# ESP32S3.net
KiCad netlist of a schematic drawn in Altium Designer
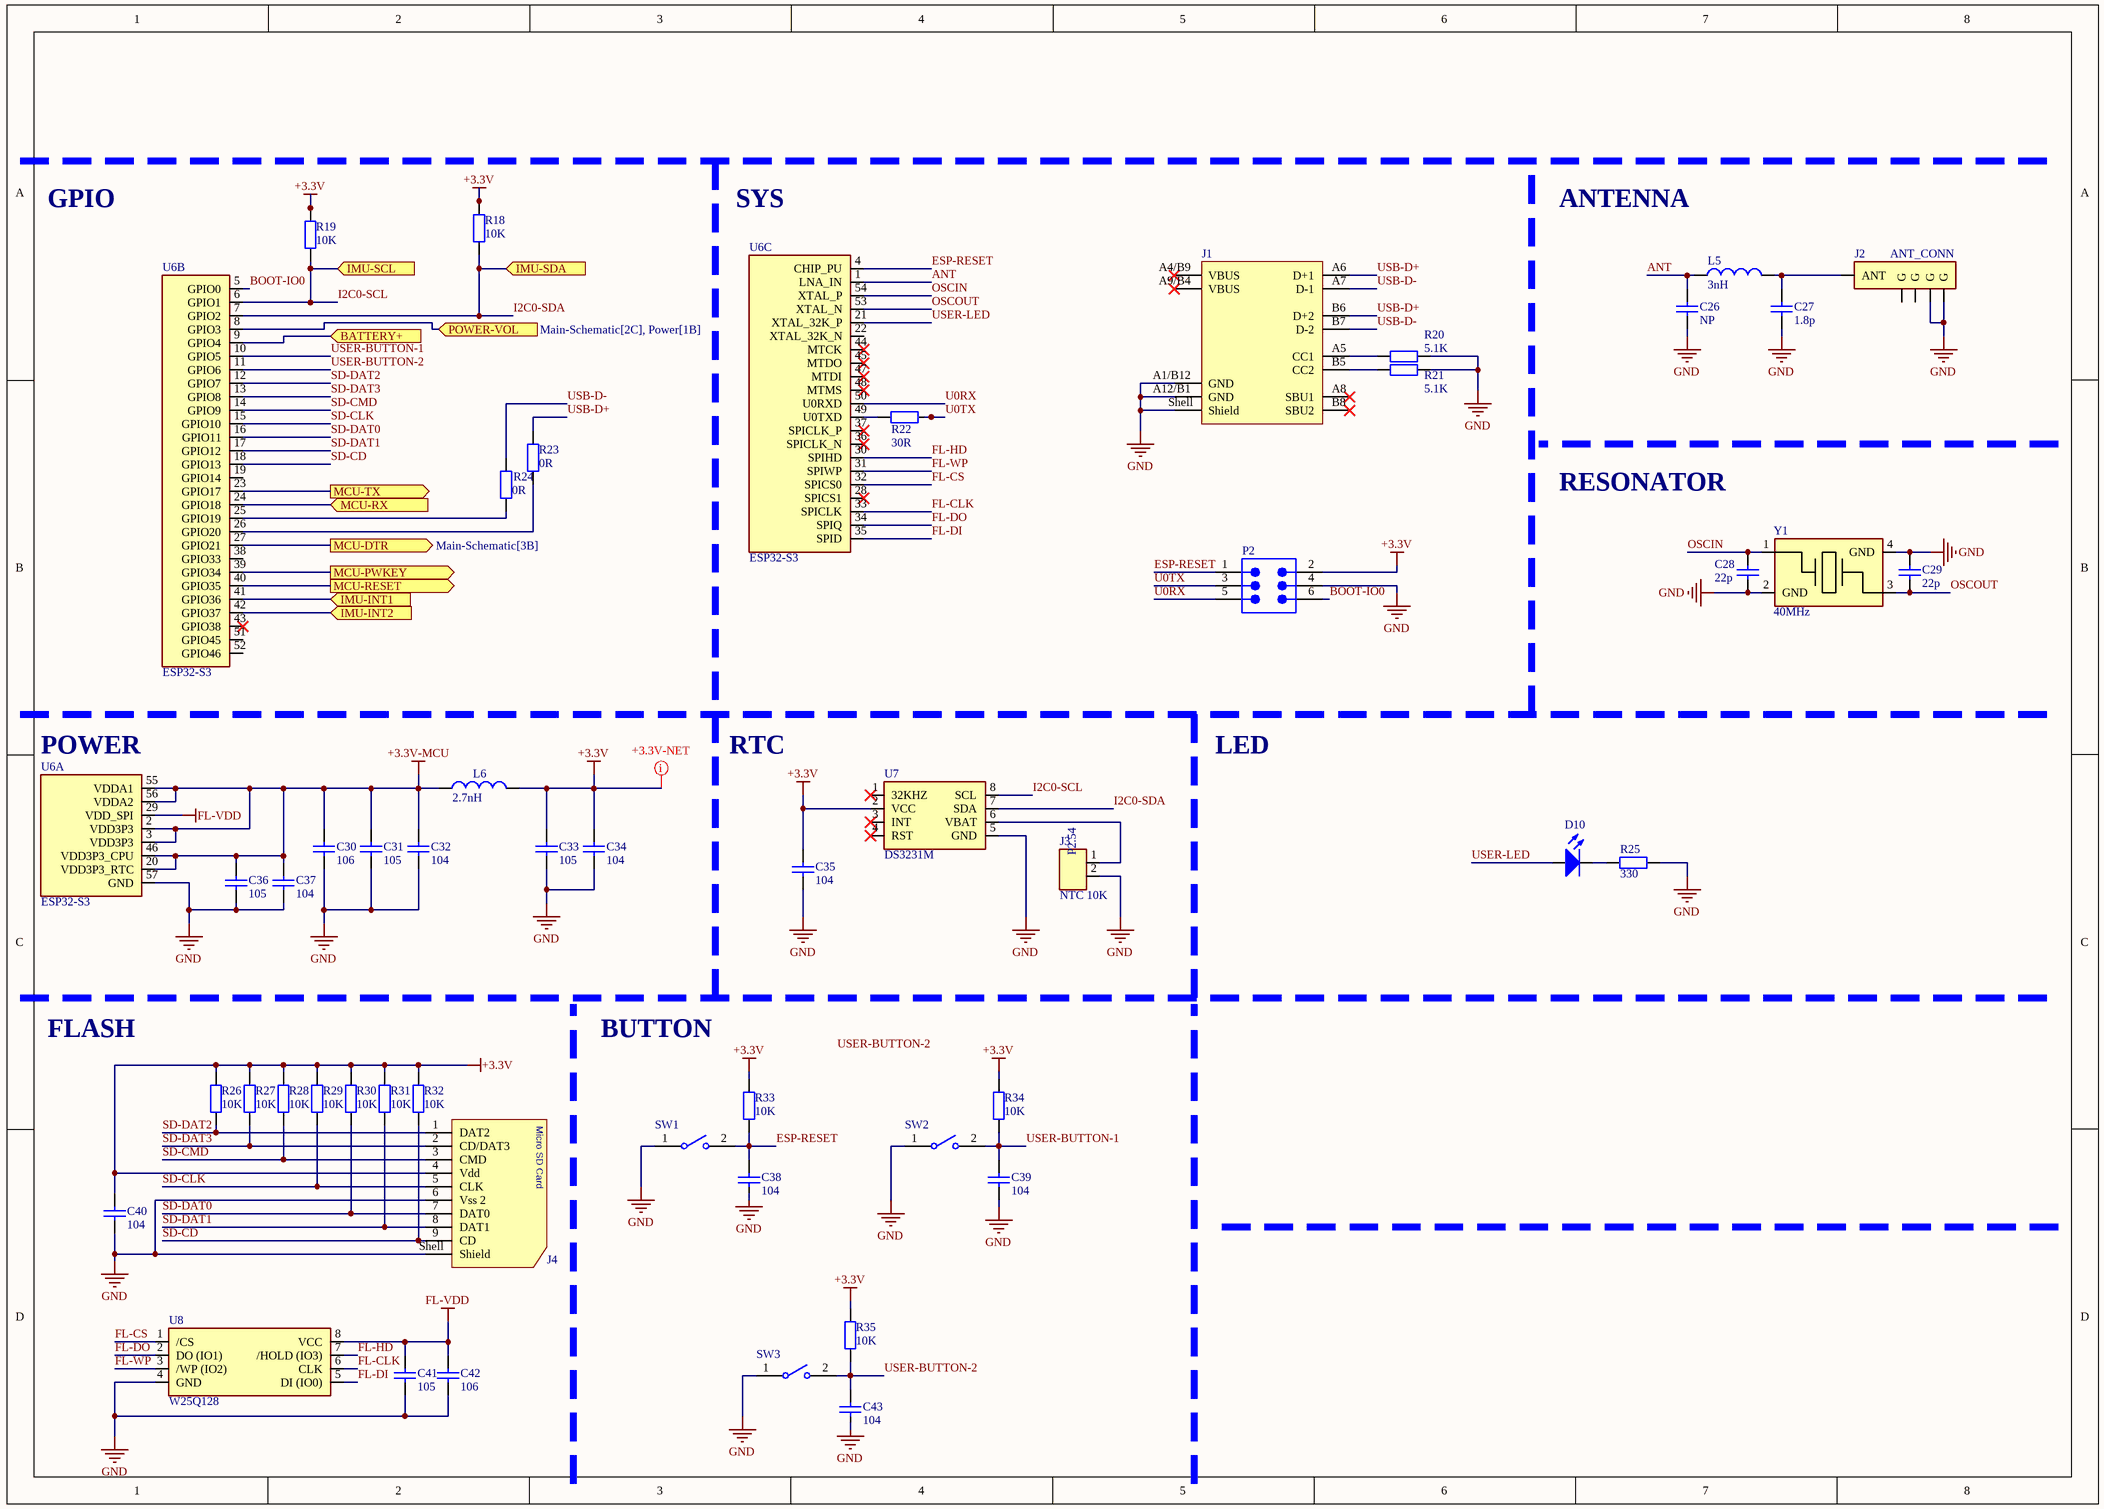
[diagram p0: ESP32S3.SchDoc]

(export (version "E")
  (design (tool "Eeschema 10.0.6"))
  (components
    (comp (ref "C26")
      (value "NP")
      (footprint "CAP_0603")
      (description "Non-polarized capacitor")
      (libsource (lib "Capacitor") (part "Cap_NP"))
    )
    (comp (ref "C27")
      (value "1.8p")
      (footprint "CAP_0603")
      (description "Non-polarized capacitor")
      (libsource (lib "Capacitor") (part "Cap_NP"))
    )
    (comp (ref "C28")
      (value "22p")
      (footprint "CAP_0603")
      (description "Non-polarized capacitor")
      (libsource (lib "Capacitor") (part "Cap_NP"))
    )
    (comp (ref "C29")
      (value "22p")
      (footprint "CAP_0603")
      (description "Non-polarized capacitor")
      (libsource (lib "Capacitor") (part "Cap_NP"))
    )
    (comp (ref "C30")
      (value "106")
      (footprint "CAP_0603")
      (description "Non-polarized capacitor")
      (libsource (lib "Capacitor") (part "Cap_NP"))
    )
    (comp (ref "C31")
      (value "105")
      (footprint "CAP_0603")
      (description "Non-polarized capacitor")
      (libsource (lib "Capacitor") (part "Cap_NP"))
    )
    (comp (ref "C32")
      (value "104")
      (footprint "CAP_0603")
      (description "Non-polarized capacitor")
      (libsource (lib "Capacitor") (part "Cap_NP"))
    )
    (comp (ref "C33")
      (value "105")
      (footprint "CAP_0603")
      (description "Non-polarized capacitor")
      (libsource (lib "Capacitor") (part "Cap_NP"))
    )
    (comp (ref "C34")
      (value "104")
      (footprint "CAP_0603")
      (description "Non-polarized capacitor")
      (libsource (lib "Capacitor") (part "Cap_NP"))
    )
    (comp (ref "C35")
      (value "104")
      (footprint "CAP_0603")
      (description "Non-polarized capacitor")
      (libsource (lib "Capacitor") (part "Cap_NP"))
    )
    (comp (ref "C36")
      (value "105")
      (footprint "CAP_0603")
      (description "Non-polarized capacitor")
      (libsource (lib "Capacitor") (part "Cap_NP"))
    )
    (comp (ref "C37")
      (value "104")
      (footprint "CAP_0603")
      (description "Non-polarized capacitor")
      (libsource (lib "Capacitor") (part "Cap_NP"))
    )
    (comp (ref "C38")
      (value "104")
      (footprint "CAP_0603")
      (description "Non-polarized capacitor")
      (libsource (lib "Capacitor") (part "Cap_NP"))
    )
    (comp (ref "C39")
      (value "104")
      (footprint "CAP_0603")
      (description "Non-polarized capacitor")
      (libsource (lib "Capacitor") (part "Cap_NP"))
    )
    (comp (ref "C40")
      (value "104")
      (footprint "CAP_0603")
      (description "Non-polarized capacitor")
      (libsource (lib "Capacitor") (part "Cap_NP"))
    )
    (comp (ref "C41")
      (value "105")
      (footprint "CAP_0603")
      (description "Non-polarized capacitor")
      (libsource (lib "Capacitor") (part "Cap_NP"))
    )
    (comp (ref "C42")
      (value "106")
      (footprint "CAP_0603")
      (description "Non-polarized capacitor")
      (libsource (lib "Capacitor") (part "Cap_NP"))
    )
    (comp (ref "C43")
      (value "104")
      (footprint "CAP_0603")
      (description "Non-polarized capacitor")
      (libsource (lib "Capacitor") (part "Cap_NP"))
    )
    (comp (ref "D10")
      (value "~")
      (footprint "LED-0805-Red")
      (description "Light Emitting Diode")
      (libsource (lib "Diode") (part "LED"))
    )
    (comp (ref "J1")
      (value "629722000214")
      (footprint "629722000214")
      (description "WR-COM USB 2.0 Type C Receptacle Horizontal SMT")
      (fields (field (name "MANUFACTURER") "Wurth Elektronik"))
      (libsource (lib "WE - Electromechanical Components") (part "USB 2.0_Type C_Receptacle_1 Port_629722000214"))
    )
    (comp (ref "J2")
      (value "ANT_CONN")
      (footprint "IPEX")
      (description "ATENNA PIN 1")
      (libsource (lib "Connector") (part "ANT_CONN"))
    )
    (comp (ref "J3")
      (value "NTC 10K")
      (footprint "XH2.54M-2")
      (libsource (lib "Connector") (part "Conn_Cai_2P_2.54"))
    )
    (comp (ref "J4")
      (value "693071040911")
      (footprint "693071040911")
      (description "WR-CRD SD Card Connector Push & Push Socket, 9 pins")
      (fields (field (name "MANUFACTURER") "Wurth Elektronik"))
      (libsource (lib "WE - Electromechanical Components") (part "Micro SD Card Socket_693071040911"))
    )
    (comp (ref "L5")
      (value "3nH")
      (footprint "INDC-0805")
      (description "Inductor")
      (fields (field (name "PUBLISHER") "Altium Limited"))
      (libsource (lib "Inductor") (part "Inductor"))
    )
    (comp (ref "L6")
      (value "2.7nH")
      (footprint "INDC-0805")
      (description "Inductor")
      (fields (field (name "PUBLISHER") "Altium Limited"))
      (libsource (lib "Inductor") (part "Inductor"))
    )
    (comp (ref "P2")
      (value "61200621621")
      (footprint "61200621621")
      (description "WR-BHD Male Box Header, THT Straight, pitch 2.54 mm, 2 Rows, 6 Pins")
      (fields (field (name "MANUFACTURER") "Wurth Elektronik"))
      (libsource (lib "WE - Electromechanical Components") (part "Header_Male_2R_06P"))
    )
    (comp (ref "R18") (value "10K") (footprint "RES_0603") (libsource (lib "Resistor") (part "Resistor")))
    (comp (ref "R19") (value "10K") (footprint "RES_0603") (libsource (lib "Resistor") (part "Resistor")))
    (comp (ref "R20") (value "5.1K") (footprint "RES_0603") (libsource (lib "") (part "Resistor_1")))
    (comp (ref "R21") (value "5.1K") (footprint "RES_0603") (libsource (lib "") (part "Resistor_1")))
    (comp (ref "R22") (value "30R") (footprint "RES_0603") (libsource (lib "") (part "Resistor_1")))
    (comp (ref "R23") (value "0R") (footprint "RES_0603") (libsource (lib "Resistor") (part "Resistor")))
    (comp (ref "R24") (value "0R") (footprint "RES_0603") (libsource (lib "Resistor") (part "Resistor")))
    (comp (ref "R25") (value "330") (footprint "RES_0603") (libsource (lib "") (part "Resistor_1")))
    (comp (ref "R26") (value "10K") (footprint "RES_0603") (libsource (lib "Resistor") (part "Resistor")))
    (comp (ref "R27") (value "10K") (footprint "RES_0603") (libsource (lib "Resistor") (part "Resistor")))
    (comp (ref "R28") (value "10K") (footprint "RES_0603") (libsource (lib "Resistor") (part "Resistor")))
    (comp (ref "R29") (value "10K") (footprint "RES_0603") (libsource (lib "Resistor") (part "Resistor")))
    (comp (ref "R30") (value "10K") (footprint "RES_0603") (libsource (lib "Resistor") (part "Resistor")))
    (comp (ref "R31") (value "10K") (footprint "RES_0603") (libsource (lib "Resistor") (part "Resistor")))
    (comp (ref "R32") (value "10K") (footprint "RES_0603") (libsource (lib "Resistor") (part "Resistor")))
    (comp (ref "R33") (value "10K") (footprint "RES_0603") (libsource (lib "Resistor") (part "Resistor")))
    (comp (ref "R34") (value "10K") (footprint "RES_0603") (libsource (lib "Resistor") (part "Resistor")))
    (comp (ref "R35") (value "10K") (footprint "RES_0603") (libsource (lib "Resistor") (part "Resistor")))
    (comp (ref "SW1")
      (value "434121050816")
      (footprint "434121050816")
      (description "WS-TASV SMT Tact Switch, 6mm x 3.5mm, 160gf, SPST-NO, 12V, 50mA")
      (fields (field (name "MANUFACTURER") "Wurth Elektronik"))
      (libsource (lib "WE - Electromechanical Components") (part "SPST-NO_2P"))
    )
    (comp (ref "SW2")
      (value "434121050816")
      (footprint "434121050816")
      (description "WS-TASV SMT Tact Switch, 6mm x 3.5mm, 160gf, SPST-NO, 12V, 50mA")
      (fields (field (name "MANUFACTURER") "Wurth Elektronik"))
      (libsource (lib "WE - Electromechanical Components") (part "SPST-NO_2P"))
    )
    (comp (ref "SW3")
      (value "434121050816")
      (footprint "434121050816")
      (description "WS-TASV SMT Tact Switch, 6mm x 3.5mm, 160gf, SPST-NO, 12V, 50mA")
      (fields (field (name "MANUFACTURER") "Wurth Elektronik"))
      (libsource (lib "WE - Electromechanical Components") (part "SPST-NO_2P"))
    )
    (comp (ref "U6") (value "ESP32-S3") (footprint "QFN56") (libsource (lib "IC") (part "ESP32-S3")))
    (comp (ref "U7")
      (value "DS3231M")
      (footprint "SOP8-P1.27")
      (description "I2C realtime clock (RTC)")
      (libsource (lib "IC") (part "DS3231M"))
    )
    (comp (ref "U8")
      (value "W25Q128")
      (footprint "SOIC127P790X216-8N")
      (description "256M-bit (32MB) Serial Flash memory")
      (libsource (lib "IC") (part "W25Q256JV"))
    )
    (comp (ref "Y1") (value "40MHz") (footprint "Y-3225") (libsource (lib "IC") (part "Resonator")))
  )
  (nets
    (net (code "1") (name "+3.3V") (class "Default")
      (node (ref "C33") (pin "2") (pinfunction "2_2") (pintype "passive"))
      (node (ref "C34") (pin "2") (pinfunction "2_2") (pintype "passive"))
      (node (ref "C35") (pin "1") (pinfunction "1_1") (pintype "passive"))
      (node (ref "C40") (pin "2") (pinfunction "2_2") (pintype "passive"))
      (node (ref "J4") (pin "4") (pinfunction "Vdd_4") (pintype "passive"))
      (node (ref "L6") (pin "2") (pinfunction "2_2") (pintype "passive"))
      (node (ref "P2") (pin "2") (pinfunction "2_2") (pintype "passive"))
      (node (ref "R18") (pin "2") (pinfunction "2_2") (pintype "passive"))
      (node (ref "R19") (pin "2") (pinfunction "2_2") (pintype "passive"))
      (node (ref "R26") (pin "2") (pinfunction "2_2") (pintype "passive"))
      (node (ref "R27") (pin "2") (pinfunction "2_2") (pintype "passive"))
      (node (ref "R28") (pin "2") (pinfunction "2_2") (pintype "passive"))
      (node (ref "R29") (pin "2") (pinfunction "2_2") (pintype "passive"))
      (node (ref "R30") (pin "2") (pinfunction "2_2") (pintype "passive"))
      (node (ref "R31") (pin "2") (pinfunction "2_2") (pintype "passive"))
      (node (ref "R32") (pin "2") (pinfunction "2_2") (pintype "passive"))
      (node (ref "R33") (pin "2") (pinfunction "2_2") (pintype "passive"))
      (node (ref "R34") (pin "2") (pinfunction "2_2") (pintype "passive"))
      (node (ref "R35") (pin "2") (pinfunction "2_2") (pintype "passive"))
      (node (ref "U7") (pin "2") (pinfunction "VCC_2") (pintype "passive"))
    )
    (net (code "2") (name "+3.3V-MCU") (class "Default")
      (node (ref "C30") (pin "2") (pinfunction "2_2") (pintype "passive"))
      (node (ref "C31") (pin "2") (pinfunction "2_2") (pintype "passive"))
      (node (ref "C32") (pin "2") (pinfunction "2_2") (pintype "passive"))
      (node (ref "C36") (pin "2") (pinfunction "2_2") (pintype "passive"))
      (node (ref "C37") (pin "2") (pinfunction "2_2") (pintype "passive"))
      (node (ref "L6") (pin "1") (pinfunction "1_1") (pintype "passive"))
      (node (ref "U6") (pin "2") (pinfunction "VDD3P3_2") (pintype "passive"))
      (node (ref "U6") (pin "20") (pinfunction "VDD3P3_RTC_20") (pintype "passive"))
      (node (ref "U6") (pin "3") (pinfunction "VDD3P3_3") (pintype "passive"))
      (node (ref "U6") (pin "46") (pinfunction "VDD3P3_CPU_46") (pintype "passive"))
      (node (ref "U6") (pin "55") (pinfunction "VDDA1_55") (pintype "passive"))
      (node (ref "U6") (pin "56") (pinfunction "VDDA2_56") (pintype "passive"))
    )
    (net (code "3") (name "/ANT") (class "Default")
      (node (ref "C26") (pin "2") (pinfunction "2_2") (pintype "passive"))
      (node (ref "L5") (pin "1") (pinfunction "1_1") (pintype "passive"))
      (node (ref "U6") (pin "1") (pinfunction "LNA_IN_1") (pintype "passive"))
    )
    (net (code "4") (name "/BATTERY+") (class "Default")
      (node (ref "U6") (pin "9") (pinfunction "GPIO4_9") (pintype "passive"))
    )
    (net (code "5") (name "/BOOT-IO0") (class "Default")
      (node (ref "P2") (pin "6") (pinfunction "6_6") (pintype "passive"))
      (node (ref "U6") (pin "5") (pinfunction "GPIO0_5") (pintype "passive"))
    )
    (net (code "6") (name "/ESP-RESET") (class "Default")
      (node (ref "C38") (pin "1") (pinfunction "1_1") (pintype "passive"))
      (node (ref "P2") (pin "1") (pinfunction "1_1") (pintype "passive"))
      (node (ref "R33") (pin "1") (pinfunction "1_1") (pintype "passive"))
      (node (ref "SW1") (pin "2") (pinfunction "2_2") (pintype "passive"))
      (node (ref "U6") (pin "4") (pinfunction "CHIP_PU_4") (pintype "passive"))
    )
    (net (code "7") (name "/FL-CLK") (class "Default")
      (node (ref "U6") (pin "33") (pinfunction "SPICLK_33") (pintype "passive"))
      (node (ref "U8") (pin "6") (pinfunction "CLK_6") (pintype "passive"))
    )
    (net (code "8") (name "/FL-CS") (class "Default")
      (node (ref "U6") (pin "32") (pinfunction "SPICS0_32") (pintype "passive"))
      (node (ref "U8") (pin "1") (pinfunction "/CS_1") (pintype "passive"))
    )
    (net (code "9") (name "/FL-DI") (class "Default")
      (node (ref "U6") (pin "35") (pinfunction "SPID_35") (pintype "passive"))
      (node (ref "U8") (pin "5") (pinfunction "DI_(IO0)_5") (pintype "passive"))
    )
    (net (code "10") (name "/FL-DO") (class "Default")
      (node (ref "U6") (pin "34") (pinfunction "SPIQ_34") (pintype "passive"))
      (node (ref "U8") (pin "2") (pinfunction "DO_(IO1)_2") (pintype "passive"))
    )
    (net (code "11") (name "/FL-HD") (class "Default")
      (node (ref "U6") (pin "30") (pinfunction "SPIHD_30") (pintype "passive"))
      (node (ref "U8") (pin "7") (pinfunction "/HOLD_(IO3)_7") (pintype "passive"))
    )
    (net (code "12") (name "/FL-WP") (class "Default")
      (node (ref "U6") (pin "31") (pinfunction "SPIWP_31") (pintype "passive"))
      (node (ref "U8") (pin "3") (pinfunction "/WP_(IO2)_3") (pintype "passive"))
    )
    (net (code "13") (name "/I2C0-SCL") (class "Default")
      (node (ref "R19") (pin "1") (pinfunction "1_1") (pintype "passive"))
      (node (ref "U6") (pin "6") (pinfunction "GPIO1_6") (pintype "passive"))
      (node (ref "U7") (pin "8") (pinfunction "SCL_8") (pintype "passive"))
    )
    (net (code "14") (name "/I2C0-SDA") (class "Default")
      (node (ref "R18") (pin "1") (pinfunction "1_1") (pintype "passive"))
      (node (ref "U6") (pin "7") (pinfunction "GPIO2_7") (pintype "passive"))
      (node (ref "U7") (pin "7") (pinfunction "SDA_7") (pintype "passive"))
    )
    (net (code "15") (name "/IMU-INT1") (class "Default")
      (node (ref "U6") (pin "41") (pinfunction "GPIO36_41") (pintype "passive"))
    )
    (net (code "16") (name "/IMU-INT2") (class "Default")
      (node (ref "U6") (pin "42") (pinfunction "GPIO37_42") (pintype "passive"))
    )
    (net (code "17") (name "/MCU-DTR") (class "Default")
      (node (ref "U6") (pin "27") (pinfunction "GPIO21_27") (pintype "passive"))
    )
    (net (code "18") (name "/MCU-PWKEY") (class "Default")
      (node (ref "U6") (pin "39") (pinfunction "GPIO34_39") (pintype "passive"))
    )
    (net (code "19") (name "/MCU-RESET") (class "Default")
      (node (ref "U6") (pin "40") (pinfunction "GPIO35_40") (pintype "passive"))
    )
    (net (code "20") (name "/MCU-RX") (class "Default")
      (node (ref "U6") (pin "24") (pinfunction "GPIO18_24") (pintype "passive"))
    )
    (net (code "21") (name "/MCU-TX") (class "Default")
      (node (ref "U6") (pin "23") (pinfunction "GPIO17_23") (pintype "passive"))
    )
    (net (code "22") (name "/OSCIN") (class "Default")
      (node (ref "C28") (pin "2") (pinfunction "2_2") (pintype "passive"))
      (node (ref "U6") (pin "54") (pinfunction "XTAL_P_54") (pintype "passive"))
      (node (ref "Y1") (pin "1") (pinfunction "OSCIN_1") (pintype "passive"))
    )
    (net (code "23") (name "/OSCOUT") (class "Default")
      (node (ref "C29") (pin "1") (pinfunction "1_1") (pintype "passive"))
      (node (ref "U6") (pin "53") (pinfunction "XTAL_N_53") (pintype "passive"))
      (node (ref "Y1") (pin "3") (pinfunction "OSCOUT_3") (pintype "passive"))
    )
    (net (code "24") (name "/POWER-VOL") (class "Default")
      (node (ref "U6") (pin "8") (pinfunction "GPIO3_8") (pintype "passive"))
    )
    (net (code "25") (name "/SD-CD") (class "Default")
      (node (ref "J4") (pin "9") (pinfunction "CD_9") (pintype "passive"))
      (node (ref "R32") (pin "1") (pinfunction "1_1") (pintype "passive"))
      (node (ref "U6") (pin "18") (pinfunction "GPIO13_18") (pintype "passive"))
    )
    (net (code "26") (name "/SD-CLK") (class "Default")
      (node (ref "J4") (pin "5") (pinfunction "CLK_5") (pintype "passive"))
      (node (ref "R29") (pin "1") (pinfunction "1_1") (pintype "passive"))
      (node (ref "U6") (pin "15") (pinfunction "GPIO10_15") (pintype "passive"))
    )
    (net (code "27") (name "/SD-CMD") (class "Default")
      (node (ref "J4") (pin "3") (pinfunction "CMD_3") (pintype "passive"))
      (node (ref "R28") (pin "1") (pinfunction "1_1") (pintype "passive"))
      (node (ref "U6") (pin "14") (pinfunction "GPIO9_14") (pintype "passive"))
    )
    (net (code "28") (name "/SD-DAT0") (class "Default")
      (node (ref "J4") (pin "7") (pinfunction "DAT0_7") (pintype "passive"))
      (node (ref "R30") (pin "1") (pinfunction "1_1") (pintype "passive"))
      (node (ref "U6") (pin "16") (pinfunction "GPIO11_16") (pintype "passive"))
    )
    (net (code "29") (name "/SD-DAT1") (class "Default")
      (node (ref "J4") (pin "8") (pinfunction "DAT1_8") (pintype "passive"))
      (node (ref "R31") (pin "1") (pinfunction "1_1") (pintype "passive"))
      (node (ref "U6") (pin "17") (pinfunction "GPIO12_17") (pintype "passive"))
    )
    (net (code "30") (name "/SD-DAT2") (class "Default")
      (node (ref "J4") (pin "1") (pinfunction "DAT2_1") (pintype "passive"))
      (node (ref "R26") (pin "1") (pinfunction "1_1") (pintype "passive"))
      (node (ref "U6") (pin "12") (pinfunction "GPIO7_12") (pintype "passive"))
    )
    (net (code "31") (name "/SD-DAT3") (class "Default")
      (node (ref "J4") (pin "2") (pinfunction "CD/DAT3_2") (pintype "passive"))
      (node (ref "R27") (pin "1") (pinfunction "1_1") (pintype "passive"))
      (node (ref "U6") (pin "13") (pinfunction "GPIO8_13") (pintype "passive"))
    )
    (net (code "32") (name "/U0RX") (class "Default")
      (node (ref "P2") (pin "5") (pinfunction "5_5") (pintype "passive"))
      (node (ref "U6") (pin "50") (pinfunction "U0RXD_50") (pintype "passive"))
    )
    (net (code "33") (name "/U0TX") (class "Default")
      (node (ref "P2") (pin "3") (pinfunction "3_3") (pintype "passive"))
      (node (ref "R22") (pin "2") (pinfunction "2_2") (pintype "passive"))
    )
    (net (code "34") (name "/USB-D+") (class "Default")
      (node (ref "J1") (pin "A6") (pinfunction "D+1_A6") (pintype "passive"))
      (node (ref "J1") (pin "B6") (pinfunction "D+2_B6") (pintype "passive"))
      (node (ref "R23") (pin "2") (pinfunction "2_2") (pintype "passive"))
    )
    (net (code "35") (name "/USB-D-") (class "Default")
      (node (ref "J1") (pin "A7") (pinfunction "D-1_A7") (pintype "passive"))
      (node (ref "J1") (pin "B7") (pinfunction "D-2_B7") (pintype "passive"))
      (node (ref "R24") (pin "2") (pinfunction "2_2") (pintype "passive"))
    )
    (net (code "36") (name "/USER-BUTTON-1") (class "Default")
      (node (ref "C39") (pin "1") (pinfunction "1_1") (pintype "passive"))
      (node (ref "R34") (pin "1") (pinfunction "1_1") (pintype "passive"))
      (node (ref "SW2") (pin "2") (pinfunction "2_2") (pintype "passive"))
      (node (ref "U6") (pin "10") (pinfunction "GPIO5_10") (pintype "passive"))
    )
    (net (code "37") (name "/USER-BUTTON-2") (class "Default")
      (node (ref "C43") (pin "1") (pinfunction "1_1") (pintype "passive"))
      (node (ref "R35") (pin "1") (pinfunction "1_1") (pintype "passive"))
      (node (ref "SW3") (pin "2") (pinfunction "2_2") (pintype "passive"))
      (node (ref "U6") (pin "11") (pinfunction "GPIO6_11") (pintype "passive"))
    )
    (net (code "38") (name "/USER-LED") (class "Default")
      (node (ref "D10") (pin "1") (pinfunction "A_1") (pintype "passive"))
      (node (ref "U6") (pin "21") (pinfunction "XTAL_32K_P_21") (pintype "passive"))
    )
    (net (code "39") (name "FL-VDD") (class "Default")
      (node (ref "C41") (pin "2") (pinfunction "2_2") (pintype "passive"))
      (node (ref "C42") (pin "2") (pinfunction "2_2") (pintype "passive"))
      (node (ref "U6") (pin "29") (pinfunction "VDD_SPI_29") (pintype "passive"))
      (node (ref "U8") (pin "8") (pinfunction "VCC_8") (pintype "passive"))
    )
    (net (code "40") (name "GND") (class "Default")
      (node (ref "C26") (pin "1") (pinfunction "1_1") (pintype "passive"))
      (node (ref "C27") (pin "1") (pinfunction "1_1") (pintype "passive"))
      (node (ref "C28") (pin "1") (pinfunction "1_1") (pintype "passive"))
      (node (ref "C29") (pin "2") (pinfunction "2_2") (pintype "passive"))
      (node (ref "C30") (pin "1") (pinfunction "1_1") (pintype "passive"))
      (node (ref "C31") (pin "1") (pinfunction "1_1") (pintype "passive"))
      (node (ref "C32") (pin "1") (pinfunction "1_1") (pintype "passive"))
      (node (ref "C33") (pin "1") (pinfunction "1_1") (pintype "passive"))
      (node (ref "C34") (pin "1") (pinfunction "1_1") (pintype "passive"))
      (node (ref "C35") (pin "2") (pinfunction "2_2") (pintype "passive"))
      (node (ref "C36") (pin "1") (pinfunction "1_1") (pintype "passive"))
      (node (ref "C37") (pin "1") (pinfunction "1_1") (pintype "passive"))
      (node (ref "C38") (pin "2") (pinfunction "2_2") (pintype "passive"))
      (node (ref "C39") (pin "2") (pinfunction "2_2") (pintype "passive"))
      (node (ref "C40") (pin "1") (pinfunction "1_1") (pintype "passive"))
      (node (ref "C41") (pin "1") (pinfunction "1_1") (pintype "passive"))
      (node (ref "C42") (pin "1") (pinfunction "1_1") (pintype "passive"))
      (node (ref "C43") (pin "2") (pinfunction "2_2") (pintype "passive"))
      (node (ref "J1") (pin "A1/B12") (pinfunction "GND_A1/B12") (pintype "passive"))
      (node (ref "J1") (pin "A12/B1") (pinfunction "GND_A12/B1") (pintype "passive"))
      (node (ref "J1") (pin "Shell") (pinfunction "Shield_Shell") (pintype "passive"))
      (node (ref "J2") (pin "4") (pinfunction "G_4") (pintype "passive"))
      (node (ref "J2") (pin "5") (pinfunction "G_5") (pintype "passive"))
      (node (ref "J3") (pin "2") (pintype "passive"))
      (node (ref "J4") (pin "6") (pinfunction "Vss_2_6") (pintype "passive"))
      (node (ref "J4") (pin "Shell") (pinfunction "Shield_Shell") (pintype "passive"))
      (node (ref "P2") (pin "4") (pinfunction "4_4") (pintype "passive"))
      (node (ref "R20") (pin "2") (pinfunction "2_2") (pintype "passive"))
      (node (ref "R21") (pin "2") (pinfunction "2_2") (pintype "passive"))
      (node (ref "R25") (pin "2") (pinfunction "2_2") (pintype "passive"))
      (node (ref "SW1") (pin "1") (pinfunction "1_1") (pintype "passive"))
      (node (ref "SW2") (pin "1") (pinfunction "1_1") (pintype "passive"))
      (node (ref "SW3") (pin "1") (pinfunction "1_1") (pintype "passive"))
      (node (ref "U6") (pin "57") (pinfunction "GND_57") (pintype "passive"))
      (node (ref "U7") (pin "5") (pinfunction "GND_5") (pintype "passive"))
      (node (ref "U8") (pin "4") (pinfunction "GND_4") (pintype "passive"))
      (node (ref "Y1") (pin "2") (pinfunction "GND_2") (pintype "passive"))
      (node (ref "Y1") (pin "4") (pinfunction "GND_4") (pintype "passive"))
    )
    (net (code "41") (name "Net-(D10-K)") (class "Default")
      (node (ref "D10") (pin "2") (pinfunction "K_2") (pintype "passive"))
      (node (ref "R25") (pin "1") (pinfunction "1_1") (pintype "passive"))
    )
    (net (code "42") (name "Net-(J1-CC1)") (class "Default")
      (node (ref "J1") (pin "A5") (pinfunction "CC1_A5") (pintype "passive"))
      (node (ref "R20") (pin "1") (pinfunction "1_1") (pintype "passive"))
    )
    (net (code "43") (name "Net-(J1-CC2)") (class "Default")
      (node (ref "J1") (pin "B5") (pinfunction "CC2_B5") (pintype "passive"))
      (node (ref "R21") (pin "1") (pinfunction "1_1") (pintype "passive"))
    )
    (net (code "44") (name "Net-(J2-ANT)") (class "Default")
      (node (ref "C27") (pin "2") (pinfunction "2_2") (pintype "passive"))
      (node (ref "J2") (pin "1") (pinfunction "ANT_1") (pintype "passive"))
      (node (ref "L5") (pin "2") (pinfunction "2_2") (pintype "passive"))
    )
    (net (code "45") (name "Net-(U6B-GPIO19)") (class "Default")
      (node (ref "R24") (pin "1") (pinfunction "1_1") (pintype "passive"))
      (node (ref "U6") (pin "25") (pinfunction "GPIO19_25") (pintype "passive"))
    )
    (net (code "46") (name "Net-(U6B-GPIO20)") (class "Default")
      (node (ref "R23") (pin "1") (pinfunction "1_1") (pintype "passive"))
      (node (ref "U6") (pin "26") (pinfunction "GPIO20_26") (pintype "passive"))
    )
    (net (code "47") (name "Net-(U6C-U0TXD)") (class "Default")
      (node (ref "R22") (pin "1") (pinfunction "1_1") (pintype "passive"))
      (node (ref "U6") (pin "49") (pinfunction "U0TXD_49") (pintype "passive"))
    )
    (net (code "48") (name "Net-(U7-VBAT)") (class "Default")
      (node (ref "J3") (pin "1") (pintype "passive"))
      (node (ref "U7") (pin "6") (pinfunction "VBAT_6") (pintype "passive"))
    )
    (net (code "49") (name "unconnected-(J1-SBU1-PadA8)") (class "Default")
      (node (ref "J1") (pin "A8") (pinfunction "SBU1_A8") (pintype "passive+no_connect"))
    )
    (net (code "50") (name "unconnected-(J1-SBU2-PadB8)") (class "Default")
      (node (ref "J1") (pin "B8") (pinfunction "SBU2_B8") (pintype "passive+no_connect"))
    )
    (net (code "51") (name "unconnected-(J1-VBUS-PadA4{slash}B9)") (class "Default")
      (node (ref "J1") (pin "A4/B9") (pinfunction "VBUS_A4/B9") (pintype "passive+no_connect"))
    )
    (net (code "52") (name "unconnected-(J1-VBUS-PadA9{slash}B4)") (class "Default")
      (node (ref "J1") (pin "A9/B4") (pinfunction "VBUS_A9/B4") (pintype "passive+no_connect"))
    )
    (net (code "53") (name "unconnected-(J2-G-Pad2)") (class "Default")
      (node (ref "J2") (pin "2") (pinfunction "G_2") (pintype "passive"))
    )
    (net (code "54") (name "unconnected-(J2-G-Pad3)") (class "Default")
      (node (ref "J2") (pin "3") (pinfunction "G_3") (pintype "passive"))
    )
    (net (code "55") (name "unconnected-(U6B-GPIO14-Pad19)") (class "Default")
      (node (ref "U6") (pin "19") (pinfunction "GPIO14_19") (pintype "passive"))
    )
    (net (code "56") (name "unconnected-(U6B-GPIO33-Pad38)") (class "Default")
      (node (ref "U6") (pin "38") (pinfunction "GPIO33_38") (pintype "passive"))
    )
    (net (code "57") (name "unconnected-(U6B-GPIO38-Pad43)") (class "Default")
      (node (ref "U6") (pin "43") (pinfunction "GPIO38_43") (pintype "passive+no_connect"))
    )
    (net (code "58") (name "unconnected-(U6B-GPIO45-Pad51)") (class "Default")
      (node (ref "U6") (pin "51") (pinfunction "GPIO45_51") (pintype "passive"))
    )
    (net (code "59") (name "unconnected-(U6B-GPIO46-Pad52)") (class "Default")
      (node (ref "U6") (pin "52") (pinfunction "GPIO46_52") (pintype "passive"))
    )
    (net (code "60") (name "unconnected-(U6C-MTCK-Pad44)") (class "Default")
      (node (ref "U6") (pin "44") (pinfunction "MTCK_44") (pintype "passive+no_connect"))
    )
    (net (code "61") (name "unconnected-(U6C-MTDI-Pad47)") (class "Default")
      (node (ref "U6") (pin "47") (pinfunction "MTDI_47") (pintype "passive+no_connect"))
    )
    (net (code "62") (name "unconnected-(U6C-MTDO-Pad45)") (class "Default")
      (node (ref "U6") (pin "45") (pinfunction "MTDO_45") (pintype "passive+no_connect"))
    )
    (net (code "63") (name "unconnected-(U6C-MTMS-Pad48)") (class "Default")
      (node (ref "U6") (pin "48") (pinfunction "MTMS_48") (pintype "passive+no_connect"))
    )
    (net (code "64") (name "unconnected-(U6C-SPICLK_N-Pad36)") (class "Default")
      (node (ref "U6") (pin "36") (pinfunction "SPICLK_N_36") (pintype "passive+no_connect"))
    )
    (net (code "65") (name "unconnected-(U6C-SPICLK_P-Pad37)") (class "Default")
      (node (ref "U6") (pin "37") (pinfunction "SPICLK_P_37") (pintype "passive+no_connect"))
    )
    (net (code "66") (name "unconnected-(U6C-SPICS1-Pad28)") (class "Default")
      (node (ref "U6") (pin "28") (pinfunction "SPICS1_28") (pintype "passive+no_connect"))
    )
    (net (code "67") (name "unconnected-(U6C-XTAL_32K_N-Pad22)") (class "Default")
      (node (ref "U6") (pin "22") (pinfunction "XTAL_32K_N_22") (pintype "passive"))
    )
    (net (code "68") (name "unconnected-(U7-32KHZ-Pad1)") (class "Default")
      (node (ref "U7") (pin "1") (pinfunction "32KHZ_1") (pintype "passive+no_connect"))
    )
    (net (code "69") (name "unconnected-(U7-INT-Pad3)") (class "Default")
      (node (ref "U7") (pin "3") (pinfunction "INT_3") (pintype "passive+no_connect"))
    )
    (net (code "70") (name "unconnected-(U7-RST-Pad4)") (class "Default")
      (node (ref "U7") (pin "4") (pinfunction "RST_4") (pintype "passive+no_connect"))
    )
  )
)
